# 06_LED_ARRAY.net
KiCad netlist of a schematic drawn in Altium Designer
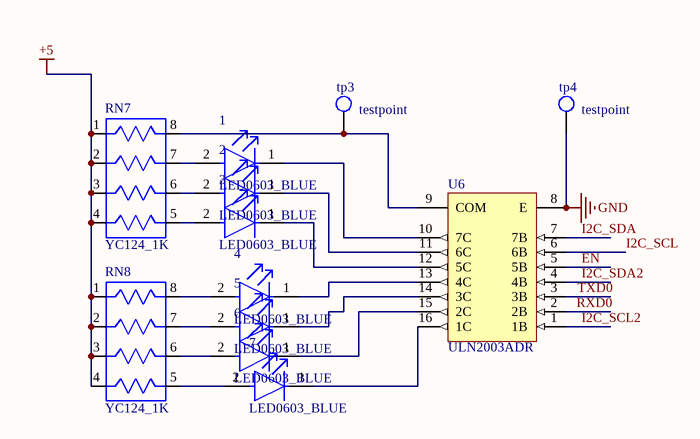
[diagram p0: 06_LED_ARRAY.SchDoc]

(export (version "E")
  (design (tool "Eeschema 10.0.6"))
  (components
    (comp (ref "1")
      (value "LED0603_BLUE")
      (footprint "FP-LTST-C191TBKT-MFG")
      (description "LED BLUE CLEAR CHIP SMD")
      (libsource (lib "Altium Content Vault") (part "8706943c75ba83719d021d2fdc84c58"))
    )
    (comp (ref "2")
      (value "LED0603_BLUE")
      (footprint "FP-LTST-C191TBKT-MFG")
      (description "LED BLUE CLEAR CHIP SMD")
      (libsource (lib "Altium Content Vault") (part "8706943c75ba83719d021d2fdc84c58"))
    )
    (comp (ref "3")
      (value "LED0603_BLUE")
      (footprint "FP-LTST-C191TBKT-MFG")
      (description "LED BLUE CLEAR CHIP SMD")
      (libsource (lib "Altium Content Vault") (part "8706943c75ba83719d021d2fdc84c58"))
    )
    (comp (ref "4")
      (value "LED0603_BLUE")
      (footprint "FP-LTST-C191TBKT-MFG")
      (description "LED BLUE CLEAR CHIP SMD")
      (libsource (lib "Altium Content Vault") (part "8706943c75ba83719d021d2fdc84c58"))
    )
    (comp (ref "5")
      (value "LED0603_BLUE")
      (footprint "FP-LTST-C191TBKT-MFG")
      (description "LED BLUE CLEAR CHIP SMD")
      (libsource (lib "Altium Content Vault") (part "8706943c75ba83719d021d2fdc84c58"))
    )
    (comp (ref "6")
      (value "LED0603_BLUE")
      (footprint "FP-LTST-C191TBKT-MFG")
      (description "LED BLUE CLEAR CHIP SMD")
      (libsource (lib "Altium Content Vault") (part "8706943c75ba83719d021d2fdc84c58"))
    )
    (comp (ref "7")
      (value "LED0603_BLUE")
      (footprint "FP-LTST-C191TBKT-MFG")
      (description "LED BLUE CLEAR CHIP SMD")
      (libsource (lib "Altium Content Vault") (part "8706943c75ba83719d021d2fdc84c58"))
    )
    (comp (ref "RN7") (value "YC124_1K") (footprint "YC124") (libsource (lib "RBS_library") (part "YC124")))
    (comp (ref "RN8") (value "YC124_1K") (footprint "YC124") (libsource (lib "RBS_library") (part "YC124")))
    (comp (ref "tp3")
      (value "testpoint")
      (footprint "testpoint_1mm")
      (libsource (lib "RBS_library") (part "testpoint"))
    )
    (comp (ref "tp4")
      (value "testpoint")
      (footprint "testpoint_1mm")
      (libsource (lib "RBS_library") (part "testpoint"))
    )
    (comp (ref "U6")
      (value "ULN2003ADR")
      (footprint "D0016A_M")
      (fields (field (name "MANUFACTURER") "TexasInstruments"))
      (libsource (lib "Altium Content Vault") (part "TI-ULX200X-D-16"))
    )
  )
  (nets
    (net (code "1") (name "+5") (class "Default")
      (node (ref "RN7") (pin "1") (pinfunction "1_1") (pintype "passive"))
      (node (ref "RN7") (pin "2") (pinfunction "2_2") (pintype "passive"))
      (node (ref "RN7") (pin "3") (pinfunction "3_3") (pintype "passive"))
      (node (ref "RN7") (pin "4") (pinfunction "4_4") (pintype "passive"))
      (node (ref "RN8") (pin "1") (pinfunction "1_1") (pintype "passive"))
      (node (ref "RN8") (pin "2") (pinfunction "2_2") (pintype "passive"))
      (node (ref "RN8") (pin "3") (pinfunction "3_3") (pintype "passive"))
      (node (ref "RN8") (pin "4") (pinfunction "4_4") (pintype "passive"))
    )
    (net (code "2") (name "/EN") (class "Default")
      (node (ref "U6") (pin "5") (pinfunction "5B_5") (pintype "input"))
    )
    (net (code "3") (name "/I2C_SCL") (class "Default")
      (node (ref "U6") (pin "6") (pinfunction "6B_6") (pintype "input"))
    )
    (net (code "4") (name "/I2C_SCL2") (class "Default")
      (node (ref "U6") (pin "1") (pinfunction "1B_1") (pintype "input"))
    )
    (net (code "5") (name "/I2C_SDA") (class "Default")
      (node (ref "U6") (pin "7") (pinfunction "7B_7") (pintype "input"))
    )
    (net (code "6") (name "/I2C_SDA2") (class "Default")
      (node (ref "U6") (pin "4") (pinfunction "4B_4") (pintype "input"))
    )
    (net (code "7") (name "/RXD0") (class "Default")
      (node (ref "U6") (pin "2") (pinfunction "2B_2") (pintype "input"))
    )
    (net (code "8") (name "/TXD0") (class "Default")
      (node (ref "U6") (pin "3") (pinfunction "3B_3") (pintype "input"))
    )
    (net (code "9") (name "GND") (class "Default")
      (node (ref "U6") (pin "8") (pinfunction "E_8") (pintype "passive"))
      (node (ref "tp4") (pin "1") (pinfunction "1_1") (pintype "passive"))
    )
    (net (code "10") (name "Net-(1-A)") (class "Default")
      (node (ref "1") (pin "2") (pinfunction "A_2") (pintype "passive"))
      (node (ref "RN7") (pin "7") (pinfunction "7_7") (pintype "passive"))
    )
    (net (code "11") (name "Net-(1-C)") (class "Default")
      (node (ref "1") (pin "1") (pinfunction "C_1") (pintype "passive"))
      (node (ref "U6") (pin "10") (pinfunction "7C_10") (pintype "output"))
    )
    (net (code "12") (name "Net-(2-A)") (class "Default")
      (node (ref "2") (pin "2") (pinfunction "A_2") (pintype "passive"))
      (node (ref "RN7") (pin "6") (pinfunction "6_6") (pintype "passive"))
    )
    (net (code "13") (name "Net-(2-C)") (class "Default")
      (node (ref "2") (pin "1") (pinfunction "C_1") (pintype "passive"))
      (node (ref "U6") (pin "11") (pinfunction "6C_11") (pintype "output"))
    )
    (net (code "14") (name "Net-(3-A)") (class "Default")
      (node (ref "3") (pin "2") (pinfunction "A_2") (pintype "passive"))
      (node (ref "RN7") (pin "5") (pinfunction "5_5") (pintype "passive"))
    )
    (net (code "15") (name "Net-(3-C)") (class "Default")
      (node (ref "3") (pin "1") (pinfunction "C_1") (pintype "passive"))
      (node (ref "U6") (pin "12") (pinfunction "5C_12") (pintype "output"))
    )
    (net (code "16") (name "Net-(4-A)") (class "Default")
      (node (ref "4") (pin "2") (pinfunction "A_2") (pintype "passive"))
      (node (ref "RN8") (pin "8") (pinfunction "8_8") (pintype "passive"))
    )
    (net (code "17") (name "Net-(4-C)") (class "Default")
      (node (ref "4") (pin "1") (pinfunction "C_1") (pintype "passive"))
      (node (ref "U6") (pin "13") (pinfunction "4C_13") (pintype "output"))
    )
    (net (code "18") (name "Net-(5-A)") (class "Default")
      (node (ref "5") (pin "2") (pinfunction "A_2") (pintype "passive"))
      (node (ref "RN8") (pin "7") (pinfunction "7_7") (pintype "passive"))
    )
    (net (code "19") (name "Net-(5-C)") (class "Default")
      (node (ref "5") (pin "1") (pinfunction "C_1") (pintype "passive"))
      (node (ref "U6") (pin "14") (pinfunction "3C_14") (pintype "output"))
    )
    (net (code "20") (name "Net-(6-A)") (class "Default")
      (node (ref "6") (pin "2") (pinfunction "A_2") (pintype "passive"))
      (node (ref "RN8") (pin "6") (pinfunction "6_6") (pintype "passive"))
    )
    (net (code "21") (name "Net-(6-C)") (class "Default")
      (node (ref "6") (pin "1") (pinfunction "C_1") (pintype "passive"))
      (node (ref "U6") (pin "15") (pinfunction "2C_15") (pintype "output"))
    )
    (net (code "22") (name "Net-(7-A)") (class "Default")
      (node (ref "7") (pin "2") (pinfunction "A_2") (pintype "passive"))
      (node (ref "RN8") (pin "5") (pinfunction "5_5") (pintype "passive"))
    )
    (net (code "23") (name "Net-(7-C)") (class "Default")
      (node (ref "7") (pin "1") (pinfunction "C_1") (pintype "passive"))
      (node (ref "U6") (pin "16") (pinfunction "1C_16") (pintype "output"))
    )
    (net (code "24") (name "Net-(U6-COM)") (class "Default")
      (node (ref "RN7") (pin "8") (pinfunction "8_8") (pintype "passive"))
      (node (ref "U6") (pin "9") (pinfunction "COM_9") (pintype "passive"))
      (node (ref "tp3") (pin "1") (pinfunction "1_1") (pintype "passive"))
    )
  )
)
